# openEPS.net
KiCad netlist of a schematic drawn in Altium Designer
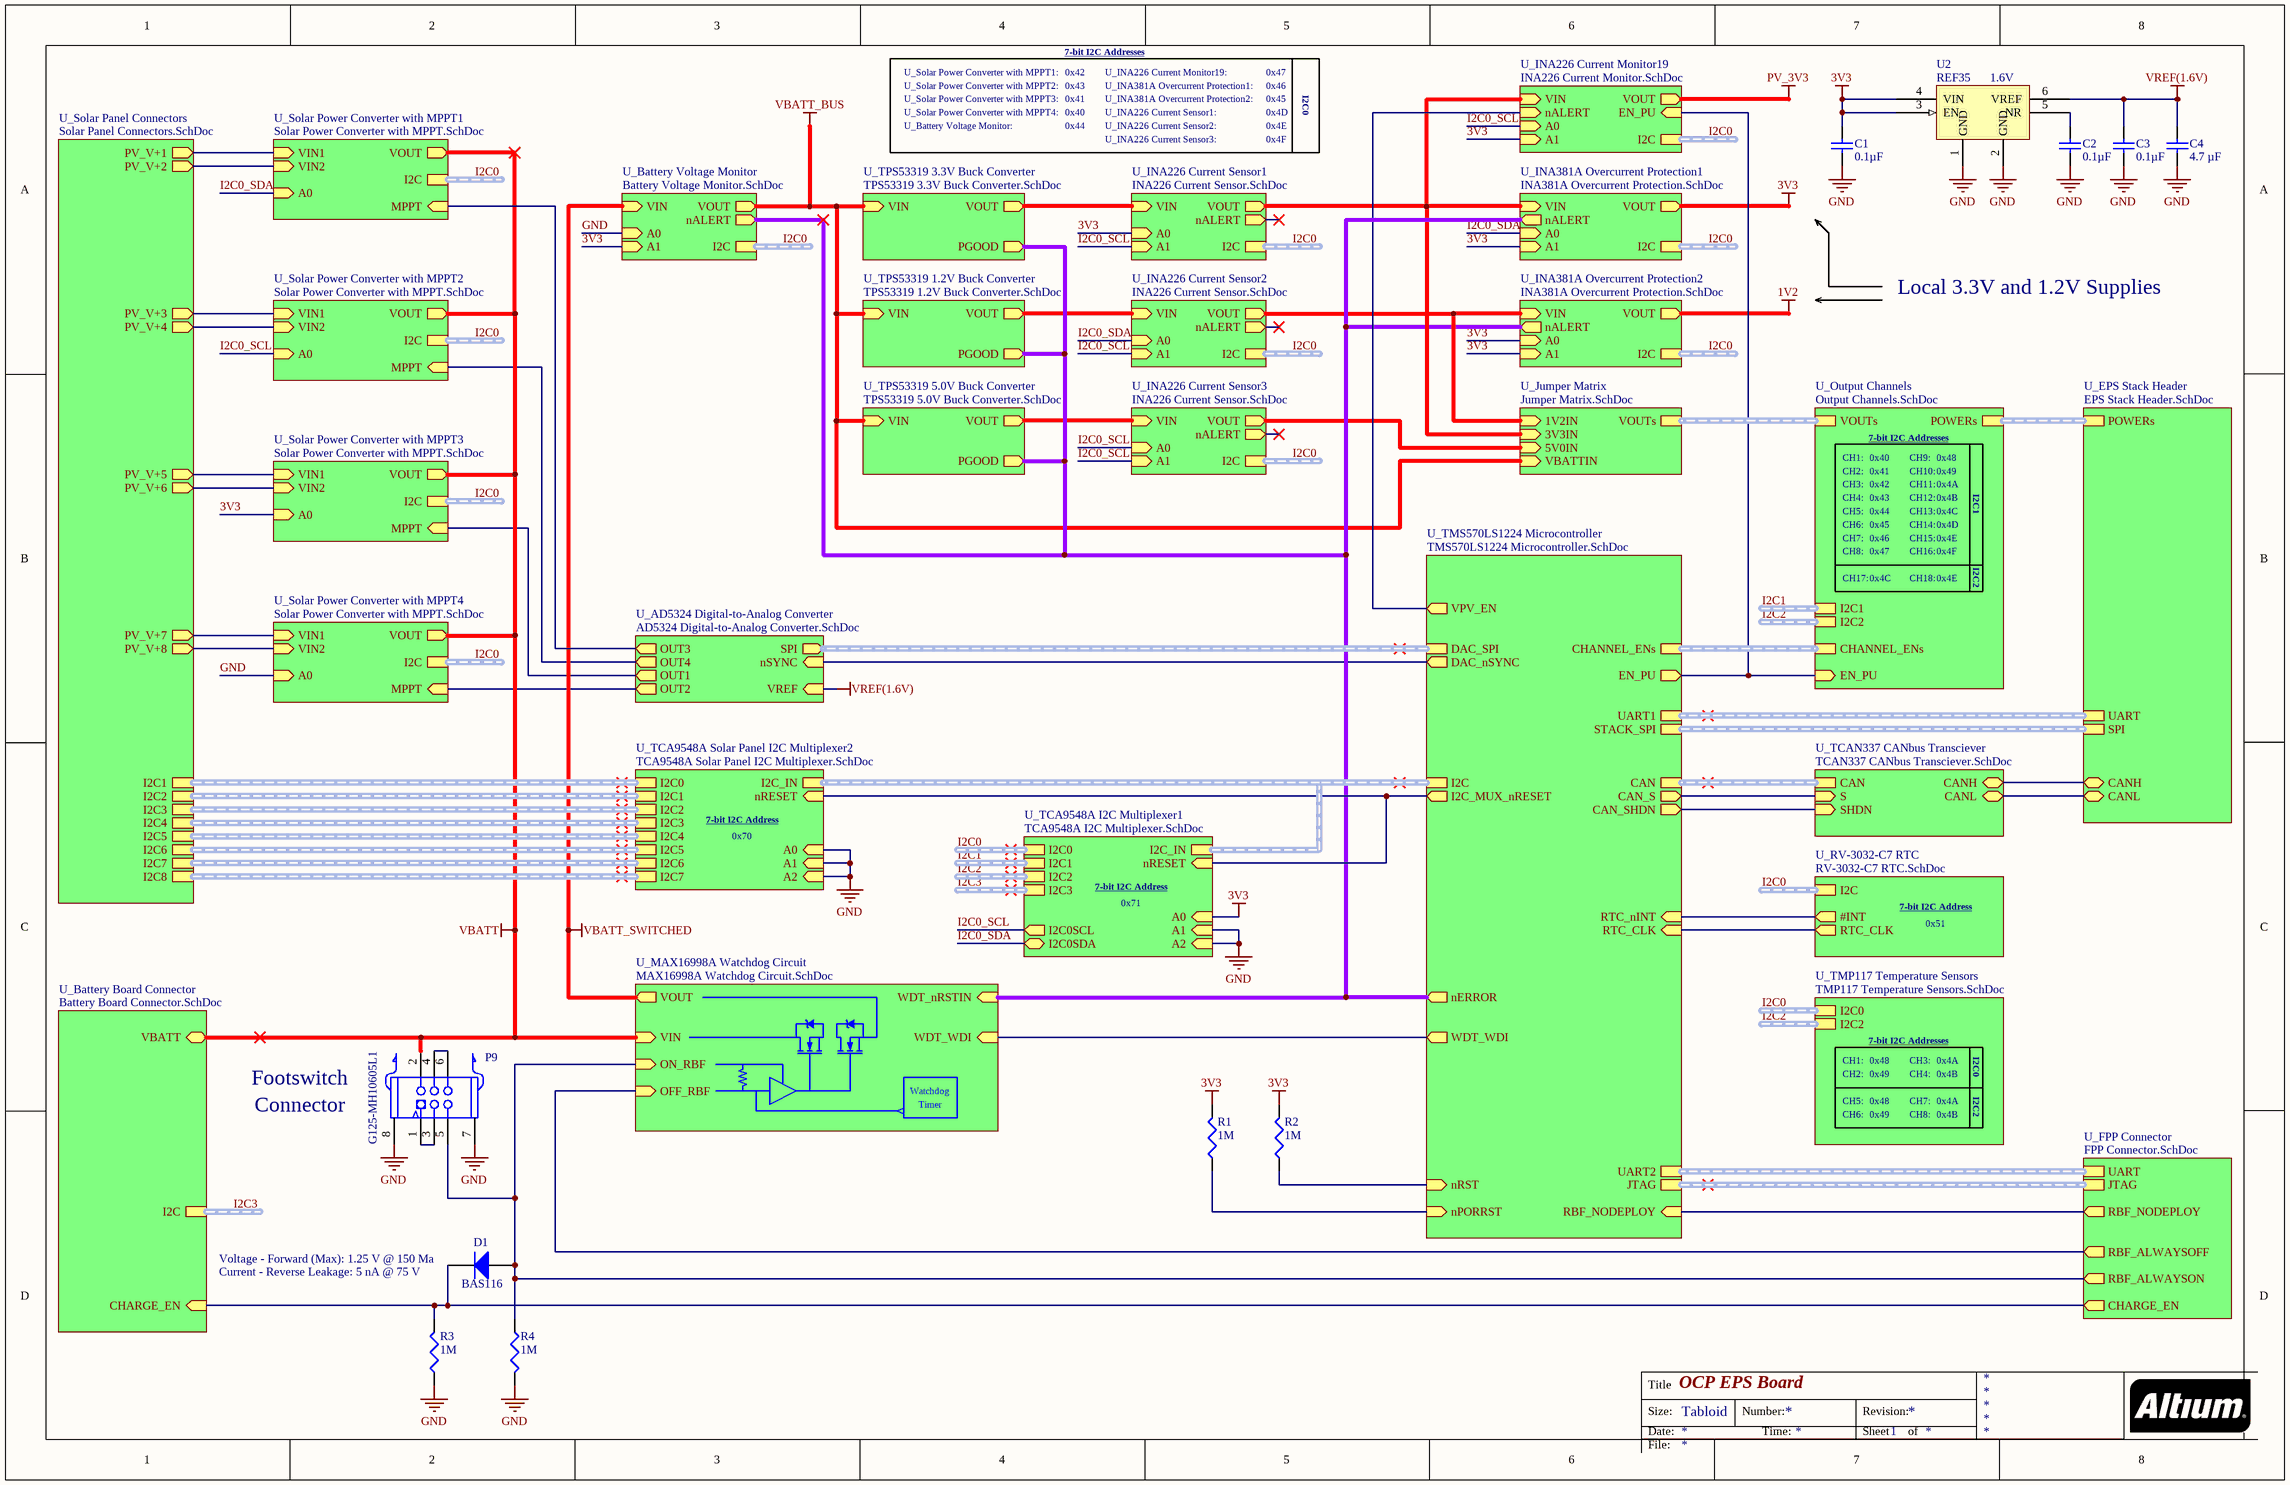
[diagram p0: openEPS.SchDoc]

(export (version "E")
  (design (tool "Eeschema 10.0.6"))
  (components
    (comp (ref "C1")
      (value "0.1µF")
      (footprint "TDK-CGA2B")
      (description "CAP CER 0.1UF 50V X7R 0402")
      (fields
        (field (name "PART NUMBER") "PC-TDK-02259")
        (field (name "MANUFACTURER PART NUMBER") "CGA2B3X7R1H104K050BB")
        (field (name "PUBLISHER") "AlbertaSat")
      )
      (libsource (lib "Database") (part "Cap"))
    )
    (comp (ref "C2")
      (value "0.1µF")
      (footprint "TDK-CGA2B")
      (description "CAP CER 0.1UF 50V X7R 0402")
      (fields
        (field (name "PART NUMBER") "PC-TDK-02259")
        (field (name "MANUFACTURER PART NUMBER") "CGA2B3X7R1H104K050BB")
        (field (name "PUBLISHER") "AlbertaSat")
      )
      (libsource (lib "Database") (part "Cap"))
    )
    (comp (ref "C3")
      (value "0.1µF")
      (footprint "TDK-CGA2B")
      (description "CAP CER 0.1UF 50V X7R 0402")
      (fields
        (field (name "PART NUMBER") "PC-TDK-02259")
        (field (name "MANUFACTURER PART NUMBER") "CGA2B3X7R1H104K050BB")
        (field (name "PUBLISHER") "AlbertaSat")
      )
      (libsource (lib "Database") (part "Cap"))
    )
    (comp (ref "C4")
      (value "4.7 µF")
      (footprint "MUR-GRM188")
      (description "CAP CER 4.7UF 16V X7R 0603")
      (fields
        (field (name "PART NUMBER") "10165")
        (field (name "MANUFACTURER PART NUMBER") "GRM188Z71C475KE21D")
        (field (name "PUBLISHER") "Altium Limited")
      )
      (libsource (lib "Database") (part "Cap"))
    )
    (comp (ref "D1")
      (value "BAS116")
      (footprint "DIOD-DFN1006-2")
      (description "DIODE GEN PURP 85V 215MA 2DFN")
      (fields
        (field (name "PART NUMBER") "61")
        (field (name "MANUFACTURER PART NUMBER") "BAS116LPH4-7B")
        (field (name "VOLTAGE - FORWARD (MAX)") "1.25 V @ 150 Ma")
        (field (name "CURRENT - REVERSE LEAKAGE") "5 nA @ 75 V")
        (field (name "PUBLISHER") "Altium Limited")
      )
      (libsource (lib "Database") (part "Diode"))
    )
    (comp (ref "P9")
      (value "G125-MH10605L1")
      (footprint "HWN-G125-MH10605L1")
      (description "CONN HEADER R/A 6POS 1.25MM")
      (fields
        (field (name "PART NUMBER") "PP-HWN-00014")
        (field (name "MANUFACTURER PART NUMBER") "G125-MH10605L1P")
        (field (name "PUBLISHER") "AlbertaSat")
      )
      (libsource (lib "Database") (part "G125-MH10605L1P"))
    )
    (comp (ref "R1")
      (value "1M")
      (footprint "PANA-ERJ2R")
      (description "RES SMD 1M OHM 1% 1/10W 0402")
      (fields
        (field (name "PART NUMBER") "19704")
        (field (name "MANUFACTURER PART NUMBER") "ERJ-2RKF1004X")
        (field (name "PUBLISHER") "Altium Limited")
      )
      (libsource (lib "Database") (part "Res3"))
    )
    (comp (ref "R2")
      (value "1M")
      (footprint "PANA-ERJ2R")
      (description "RES SMD 1M OHM 1% 1/10W 0402")
      (fields
        (field (name "PART NUMBER") "19704")
        (field (name "MANUFACTURER PART NUMBER") "ERJ-2RKF1004X")
        (field (name "PUBLISHER") "Altium Limited")
      )
      (libsource (lib "Database") (part "Res3"))
    )
    (comp (ref "R3")
      (value "1M")
      (footprint "PANA-ERJ2R")
      (description "RES SMD 1M OHM 1% 1/10W 0402")
      (fields
        (field (name "PART NUMBER") "19704")
        (field (name "MANUFACTURER PART NUMBER") "ERJ-2RKF1004X")
        (field (name "PUBLISHER") "Altium Limited")
      )
      (libsource (lib "Database") (part "Res3"))
    )
    (comp (ref "R4")
      (value "1M")
      (footprint "PANA-ERJ2R")
      (description "RES SMD 1M OHM 1% 1/10W 0402")
      (fields
        (field (name "PART NUMBER") "19704")
        (field (name "MANUFACTURER PART NUMBER") "ERJ-2RKF1004X")
        (field (name "PUBLISHER") "Altium Limited")
      )
      (libsource (lib "Database") (part "Res3"))
    )
    (comp (ref "U2")
      (value "REF35")
      (footprint "TI-DBV0006A")
      (description "650-NA QUIESCENT CURRENT, 12-PPM")
      (fields
        (field (name "PART NUMBER") "150")
        (field (name "MANUFACTURER PART NUMBER") "REF35160QDBVR")
        (field (name "ALTIUM_VALUE") "1.6V")
      )
      (libsource (lib "Database") (part "REF35xxxQDBVR"))
    )
  )
  (nets
    (net (code "12") (name "/CHARGE_EN") (class "Default")
      (node (ref "D1") (pin "2") (pinfunction "K_2") (pintype "passive"))
      (node (ref "R3") (pin "2") (pinfunction "2_2") (pintype "passive"))
    )
    (net (code "43") (name "/RBF_ALWAYSON") (class "Default")
      (node (ref "D1") (pin "1") (pinfunction "A_1") (pintype "passive"))
      (node (ref "P9") (pin "5") (pinfunction "5_5") (pintype "passive"))
      (node (ref "R4") (pin "1") (pinfunction "1_1") (pintype "passive"))
    )
    (net (code "62") (name "/nPORRST") (class "Default")
      (node (ref "R1") (pin "2") (pinfunction "2_2") (pintype "passive"))
    )
    (net (code "63") (name "/nRST") (class "Default")
      (node (ref "R2") (pin "2") (pinfunction "2_2") (pintype "passive"))
    )
    (net (code "69") (name "3V3") (class "Default")
      (node (ref "C1") (pin "1") (pinfunction "1_1") (pintype "passive"))
      (node (ref "R1") (pin "1") (pinfunction "1_1") (pintype "passive"))
      (node (ref "R2") (pin "1") (pinfunction "1_1") (pintype "passive"))
      (node (ref "U2") (pin "3") (pinfunction "EN_3") (pintype "input"))
      (node (ref "U2") (pin "4") (pinfunction "VIN_4") (pintype "power_in"))
    )
    (net (code "70") (name "GND") (class "Default")
      (node (ref "C1") (pin "2") (pinfunction "2_2") (pintype "passive"))
      (node (ref "C2") (pin "2") (pinfunction "2_2") (pintype "passive"))
      (node (ref "C3") (pin "2") (pinfunction "2_2") (pintype "passive"))
      (node (ref "C4") (pin "1") (pinfunction "1_1") (pintype "passive"))
      (node (ref "P9") (pin "7") (pinfunction "7_7") (pintype "passive"))
      (node (ref "P9") (pin "8") (pinfunction "8_8") (pintype "passive"))
      (node (ref "R3") (pin "1") (pinfunction "1_1") (pintype "passive"))
      (node (ref "R4") (pin "2") (pinfunction "2_2") (pintype "passive"))
      (node (ref "U2") (pin "1") (pinfunction "GND_1") (pintype "power_in"))
      (node (ref "U2") (pin "2") (pinfunction "GND_2") (pintype "power_in"))
    )
    (net (code "71") (name "Net-(P9-Pad1)") (class "Default")
      (node (ref "P9") (pin "1") (pinfunction "1_1") (pintype "passive"))
      (node (ref "P9") (pin "3") (pinfunction "3_3") (pintype "passive"))
    )
    (net (code "72") (name "Net-(P9-Pad4)") (class "Default")
      (node (ref "P9") (pin "4") (pinfunction "4_4") (pintype "passive"))
      (node (ref "P9") (pin "6") (pinfunction "6_6") (pintype "passive"))
    )
    (net (code "73") (name "Net-(U2-NR)") (class "Default")
      (node (ref "C2") (pin "1") (pinfunction "1_1") (pintype "passive"))
      (node (ref "U2") (pin "5") (pinfunction "NR_5") (pintype "power_in"))
    )
    (net (code "75") (name "VBATT") (class "Default")
      (node (ref "P9") (pin "2") (pinfunction "2_2") (pintype "passive"))
    )
    (net (code "78") (name "VREF(1.6V)") (class "Default")
      (node (ref "C3") (pin "1") (pinfunction "1_1") (pintype "passive"))
      (node (ref "C4") (pin "2") (pinfunction "2_2") (pintype "passive"))
      (node (ref "U2") (pin "6") (pinfunction "VREF_6") (pintype "power_in"))
    )
  )
)
